# OScope_SoundCard.net
KiCad netlist of a schematic drawn in EAGLE
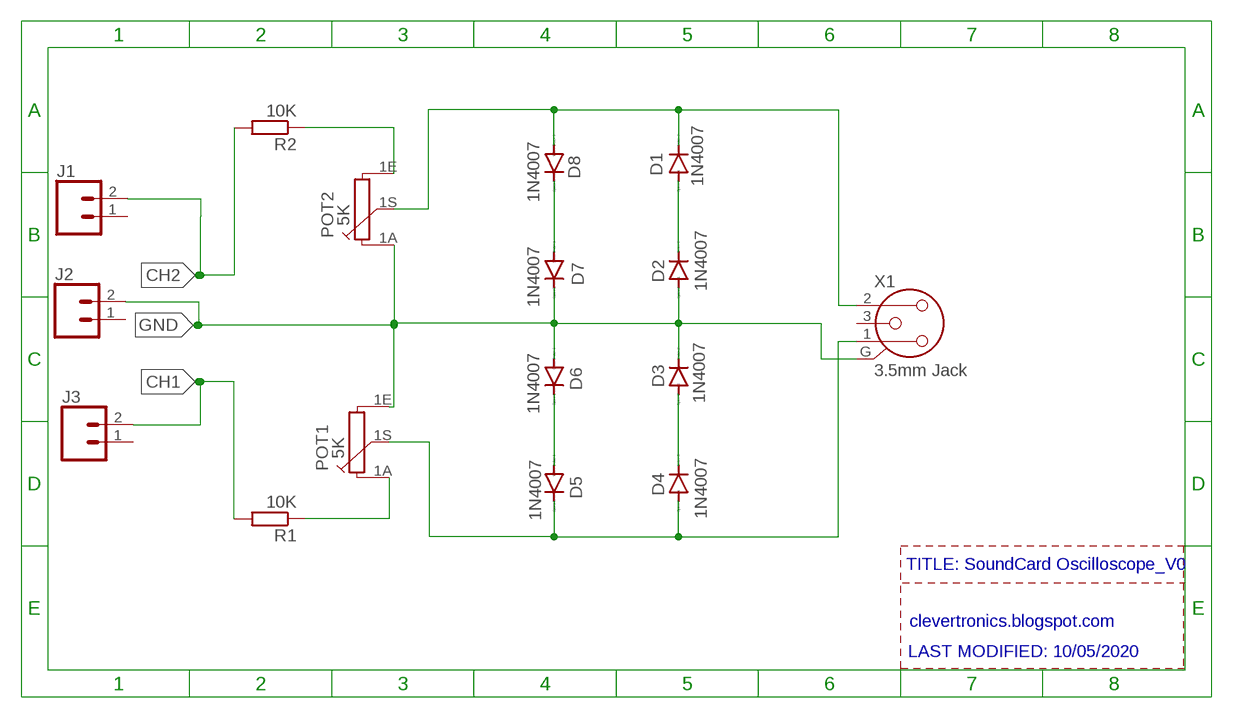
[diagram p0: schematic, sheet 1]

(export (version "E")
  (design (tool "Eeschema 10.0.6"))
  (components
    (comp (ref "D1")
      (value "1N4007")
      (footprint "eagle-import:DO41-10")
      (libsource (lib "eagle-import") (part "1N4004"))
    )
    (comp (ref "D2")
      (value "1N4007")
      (footprint "eagle-import:DO41-10")
      (libsource (lib "eagle-import") (part "1N4004"))
    )
    (comp (ref "D3")
      (value "1N4007")
      (footprint "eagle-import:DO41-10")
      (libsource (lib "eagle-import") (part "1N4004"))
    )
    (comp (ref "D4")
      (value "1N4007")
      (footprint "eagle-import:DO41-10")
      (libsource (lib "eagle-import") (part "1N4004"))
    )
    (comp (ref "D5")
      (value "1N4007")
      (footprint "eagle-import:DO41-10")
      (libsource (lib "eagle-import") (part "1N4004"))
    )
    (comp (ref "D6")
      (value "1N4007")
      (footprint "eagle-import:DO41-10")
      (libsource (lib "eagle-import") (part "1N4004"))
    )
    (comp (ref "D7")
      (value "1N4007")
      (footprint "eagle-import:DO41-10")
      (libsource (lib "eagle-import") (part "1N4004"))
    )
    (comp (ref "D8")
      (value "1N4007")
      (footprint "eagle-import:DO41-10")
      (libsource (lib "eagle-import") (part "1N4004"))
    )
    (comp (ref "J1")
      (value "CONN_023.5MM")
      (footprint "eagle-import:SCREWTERMINAL-3.5MM-2")
      (libsource (lib "eagle-import") (part "CONN_023.5MM"))
    )
    (comp (ref "J2")
      (value "CONN_023.5MM")
      (footprint "eagle-import:SCREWTERMINAL-3.5MM-2")
      (libsource (lib "eagle-import") (part "CONN_023.5MM"))
    )
    (comp (ref "J3")
      (value "CONN_023.5MM")
      (footprint "eagle-import:SCREWTERMINAL-3.5MM-2")
      (libsource (lib "eagle-import") (part "CONN_023.5MM"))
    )
    (comp (ref "POT1")
      (value "5K")
      (footprint "eagle-import:PC16S")
      (libsource (lib "eagle-import") (part "PC16S"))
    )
    (comp (ref "POT2")
      (value "5K")
      (footprint "eagle-import:PC16S")
      (libsource (lib "eagle-import") (part "PC16S"))
    )
    (comp (ref "R1")
      (value "10K")
      (footprint "eagle-import:0207_10")
      (libsource (lib "eagle-import") (part "R-EU_0207/10"))
    )
    (comp (ref "R2")
      (value "10K")
      (footprint "eagle-import:0207_10")
      (libsource (lib "eagle-import") (part "R-EU_0207/10"))
    )
    (comp (ref "X1")
      (value "3.5mm Jack")
      (footprint "eagle-import:NC3FAH2")
      (fields (field (name "MPN") "NC3FAH2"))
      (libsource (lib "eagle-import") (part "NC3FAH2"))
    )
  )
  (nets
    (net (code "1") (name "CH1") (class "Default")
      (node (ref "J3") (pin "2") (pinfunction "2_2") (pintype "passive"))
      (node (ref "R1") (pin "2") (pinfunction "2_2") (pintype "passive"))
    )
    (net (code "2") (name "CH2") (class "Default")
      (node (ref "J1") (pin "2") (pinfunction "2_2") (pintype "passive"))
      (node (ref "R2") (pin "2") (pinfunction "2_2") (pintype "passive"))
    )
    (net (code "4") (name "Net-(D1-PadA)") (class "Default")
      (node (ref "D1") (pin "A") (pinfunction "A_A") (pintype "passive"))
      (node (ref "D2") (pin "C") (pinfunction "C_C") (pintype "passive"))
    )
    (net (code "5") (name "Net-(D2-PadA)") (class "Default")
      (node (ref "D2") (pin "A") (pinfunction "A_A") (pintype "passive"))
      (node (ref "D3") (pin "C") (pinfunction "C_C") (pintype "passive"))
      (node (ref "D6") (pin "A") (pinfunction "A_A") (pintype "passive"))
      (node (ref "D7") (pin "C") (pinfunction "C_C") (pintype "passive"))
      (node (ref "J2") (pin "2") (pinfunction "2_2") (pintype "passive"))
      (node (ref "POT1") (pin "1E") (pinfunction "1E_1E") (pintype "passive"))
      (node (ref "POT2") (pin "1A") (pinfunction "1A_1A") (pintype "passive"))
      (node (ref "X1") (pin "G") (pinfunction "G_G") (pintype "passive"))
    )
    (net (code "6") (name "Net-(D3-PadA)") (class "Default")
      (node (ref "D3") (pin "A") (pinfunction "A_A") (pintype "passive"))
      (node (ref "D4") (pin "C") (pinfunction "C_C") (pintype "passive"))
    )
    (net (code "7") (name "Net-(D5-PadA)") (class "Default")
      (node (ref "D5") (pin "A") (pinfunction "A_A") (pintype "passive"))
      (node (ref "D6") (pin "C") (pinfunction "C_C") (pintype "passive"))
    )
    (net (code "8") (name "Net-(D7-PadA)") (class "Default")
      (node (ref "D7") (pin "A") (pinfunction "A_A") (pintype "passive"))
      (node (ref "D8") (pin "C") (pinfunction "C_C") (pintype "passive"))
    )
    (net (code "9") (name "Net-(POT1-Pad1A)") (class "Default")
      (node (ref "POT1") (pin "1A") (pinfunction "1A_1A") (pintype "passive"))
      (node (ref "R1") (pin "1") (pinfunction "1_1") (pintype "passive"))
    )
    (net (code "10") (name "Net-(POT2-Pad1E)") (class "Default")
      (node (ref "POT2") (pin "1E") (pinfunction "1E_1E") (pintype "passive"))
      (node (ref "R2") (pin "1") (pinfunction "1_1") (pintype "passive"))
    )
    (net (code "11") (name "Net-(X1-1)") (class "Default")
      (node (ref "D1") (pin "C") (pinfunction "C_C") (pintype "passive"))
      (node (ref "D8") (pin "A") (pinfunction "A_A") (pintype "passive"))
      (node (ref "POT2") (pin "1S") (pinfunction "1S_1S") (pintype "passive"))
      (node (ref "X1") (pin "2") (pinfunction "1_2") (pintype "passive"))
    )
    (net (code "12") (name "Net-(X1-2)") (class "Default")
      (node (ref "D4") (pin "A") (pinfunction "A_A") (pintype "passive"))
      (node (ref "D5") (pin "C") (pinfunction "C_C") (pintype "passive"))
      (node (ref "POT1") (pin "1S") (pinfunction "1S_1S") (pintype "passive"))
      (node (ref "X1") (pin "1") (pinfunction "2_1") (pintype "passive"))
    )
    (net (code "13") (name "unconnected-(J1-Pad1)") (class "Default")
      (node (ref "J1") (pin "1") (pinfunction "1_1") (pintype "passive"))
    )
    (net (code "14") (name "unconnected-(J2-Pad1)") (class "Default")
      (node (ref "J2") (pin "1") (pinfunction "1_1") (pintype "passive"))
    )
    (net (code "15") (name "unconnected-(J3-Pad1)") (class "Default")
      (node (ref "J3") (pin "1") (pinfunction "1_1") (pintype "passive"))
    )
    (net (code "16") (name "unconnected-(X1-Pad3)") (class "Default")
      (node (ref "X1") (pin "3") (pinfunction "3_3") (pintype "passive"))
    )
  )
)
